# AP62500_6V.net
KiCad netlist of a schematic drawn in Altium Designer
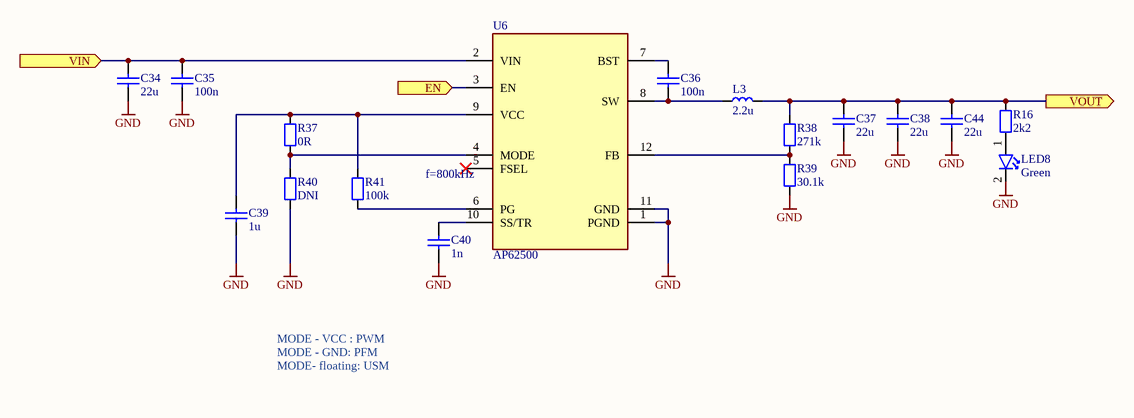
[diagram p0: AP62500_6V.SchDoc]

(export (version "E")
  (design (tool "Eeschema 10.0.6"))
  (components
    (comp (ref "C34")
      (value "22u")
      (footprint "C_1206_3216Metric_IPC_N")
      (description "Generic MLCC with 1206 Footprint")
      (libsource (lib "database_library") (part "Capacitor_unpol"))
    )
    (comp (ref "C35")
      (value "100n")
      (footprint "C_0603_1608Metric_IPC_N")
      (description "Generic MLCC with 0603 Footprint")
      (libsource (lib "database_library") (part "Capacitor_unpol"))
    )
    (comp (ref "C36")
      (value "100n")
      (footprint "C_0402_1005Metric_IPC_N")
      (description "Generic MLCC with 0402 Footprint")
      (libsource (lib "database_library") (part "Capacitor_unpol"))
    )
    (comp (ref "C37")
      (value "22u")
      (footprint "C_1206_3216Metric_IPC_N")
      (description "Generic MLCC with 1206 Footprint")
      (libsource (lib "database_library") (part "Capacitor_unpol"))
    )
    (comp (ref "C38")
      (value "22u")
      (footprint "C_1206_3216Metric_IPC_N")
      (description "Generic MLCC with 1206 Footprint")
      (libsource (lib "database_library") (part "Capacitor_unpol"))
    )
    (comp (ref "C39")
      (value "1u")
      (footprint "C_0603_1608Metric_IPC_N")
      (description "Generic MLCC with 0603 Footprint")
      (libsource (lib "database_library") (part "Capacitor_unpol"))
    )
    (comp (ref "C40")
      (value "1n")
      (footprint "C_0402_1005Metric_IPC_N")
      (description "Generic MLCC with 0402 Footprint")
      (libsource (lib "database_library") (part "Capacitor_unpol"))
    )
    (comp (ref "C44")
      (value "22u")
      (footprint "C_1206_3216Metric_IPC_N")
      (description "Generic MLCC with 1206 Footprint")
      (libsource (lib "database_library") (part "Capacitor_unpol"))
    )
    (comp (ref "L3")
      (value "2.2u")
      (footprint "AVX_LMLP07A7")
      (description "Power Inductor, 2.2u, 8A, -, 20m, 20%, LMLP07A7")
      (fields (field (name "TOLERANCE") "20%") (field (name "MANUFACTURER") "Kyocera/AVX"))
      (libsource (lib "database_library") (part "Inductor"))
    )
    (comp (ref "LED8")
      (value "Green")
      (footprint "LED_0603_1806Metric_IPC_N")
      (description "MLCC, Low Current, Green, 2.2V, 20mA, 0603")
      (fields
        (field (name "MANUFACTURER") "Broadcom / Avago")
        (field (name "MANUFACTURER PART NUMBER") "HSMG-C190")
      )
      (libsource (lib "database_library") (part "LED"))
    )
    (comp (ref "R16")
      (value "2k2")
      (footprint "R_0402_1005Metric_IPC_N")
      (description "Generic Chip Resistor with 0402 Footprint")
      (libsource (lib "database_library") (part "Resistor"))
    )
    (comp (ref "R37")
      (value "0R")
      (footprint "R_0402_1005Metric_IPC_N")
      (description "Generic Chip Resistor with 0402 Footprint")
      (libsource (lib "database_library") (part "Resistor"))
    )
    (comp (ref "R38")
      (value "271k")
      (footprint "R_0402_1005Metric_IPC_N")
      (description "Generic Chip Resistor with 0402 Footprint")
      (libsource (lib "database_library") (part "Resistor"))
    )
    (comp (ref "R39")
      (value "30.1k")
      (footprint "R_0402_1005Metric_IPC_N")
      (description "Generic Chip Resistor with 0402 Footprint")
      (libsource (lib "database_library") (part "Resistor"))
    )
    (comp (ref "R40")
      (value "DNI")
      (footprint "R_0402_1005Metric_IPC_N")
      (description "Generic Chip Resistor with 0402 Footprint")
      (libsource (lib "database_library") (part "Resistor"))
    )
    (comp (ref "R41")
      (value "100k")
      (footprint "R_0402_1005Metric_IPC_N")
      (description "Generic Chip Resistor with 0402 Footprint")
      (libsource (lib "database_library") (part "Resistor"))
    )
    (comp (ref "U6")
      (value "AP62500")
      (footprint "V-QFN2030-12-Type-A_3.05x2.05mm_P0.5mm")
      (fields (field (name "MANUFACTURER") "Diodes Incorporated"))
      (libsource (lib "database_library") (part "AP62500"))
    )
  )
  (nets
    (net (code "1") (name "/EN") (class "Default")
      (node (ref "U6") (pin "3") (pinfunction "EN_3") (pintype "passive"))
    )
    (net (code "2") (name "/VIN") (class "Default")
      (node (ref "C34") (pin "2") (pinfunction "2_2") (pintype "passive"))
      (node (ref "C35") (pin "2") (pinfunction "2_2") (pintype "passive"))
      (node (ref "U6") (pin "2") (pinfunction "VIN_2") (pintype "passive"))
    )
    (net (code "3") (name "/VOUT") (class "Default")
      (node (ref "C37") (pin "2") (pinfunction "2_2") (pintype "passive"))
      (node (ref "C38") (pin "2") (pinfunction "2_2") (pintype "passive"))
      (node (ref "C44") (pin "2") (pinfunction "2_2") (pintype "passive"))
      (node (ref "L3") (pin "2") (pinfunction "2_2") (pintype "passive"))
      (node (ref "R16") (pin "1") (pinfunction "1_1") (pintype "passive"))
      (node (ref "R38") (pin "2") (pinfunction "2_2") (pintype "passive"))
    )
    (net (code "4") (name "GND") (class "Default")
      (node (ref "C34") (pin "1") (pinfunction "1_1") (pintype "passive"))
      (node (ref "C35") (pin "1") (pinfunction "1_1") (pintype "passive"))
      (node (ref "C37") (pin "1") (pinfunction "1_1") (pintype "passive"))
      (node (ref "C38") (pin "1") (pinfunction "1_1") (pintype "passive"))
      (node (ref "C39") (pin "1") (pinfunction "1_1") (pintype "passive"))
      (node (ref "C40") (pin "1") (pinfunction "1_1") (pintype "passive"))
      (node (ref "C44") (pin "1") (pinfunction "1_1") (pintype "passive"))
      (node (ref "LED8") (pin "2") (pinfunction "2_2") (pintype "passive"))
      (node (ref "R39") (pin "1") (pinfunction "1_1") (pintype "passive"))
      (node (ref "R40") (pin "1") (pinfunction "1_1") (pintype "passive"))
      (node (ref "U6") (pin "1") (pinfunction "PGND_1") (pintype "passive"))
      (node (ref "U6") (pin "11") (pinfunction "GND_11") (pintype "passive"))
    )
    (net (code "5") (name "Net-(LED8-Pad1)") (class "Default")
      (node (ref "LED8") (pin "1") (pinfunction "1_1") (pintype "passive"))
      (node (ref "R16") (pin "2") (pinfunction "2_2") (pintype "passive"))
    )
    (net (code "6") (name "Net-(U6-BST)") (class "Default")
      (node (ref "C36") (pin "2") (pinfunction "2_2") (pintype "passive"))
      (node (ref "U6") (pin "7") (pinfunction "BST_7") (pintype "passive"))
    )
    (net (code "7") (name "Net-(U6-FB)") (class "Default")
      (node (ref "R38") (pin "1") (pinfunction "1_1") (pintype "passive"))
      (node (ref "R39") (pin "2") (pinfunction "2_2") (pintype "passive"))
      (node (ref "U6") (pin "12") (pinfunction "FB_12") (pintype "passive"))
    )
    (net (code "8") (name "Net-(U6-MODE)") (class "Default")
      (node (ref "R37") (pin "1") (pinfunction "1_1") (pintype "passive"))
      (node (ref "R40") (pin "2") (pinfunction "2_2") (pintype "passive"))
      (node (ref "U6") (pin "4") (pinfunction "MODE_4") (pintype "passive"))
    )
    (net (code "9") (name "Net-(U6-PG)") (class "Default")
      (node (ref "R41") (pin "1") (pinfunction "1_1") (pintype "passive"))
      (node (ref "U6") (pin "6") (pinfunction "PG_6") (pintype "open_collector"))
    )
    (net (code "10") (name "Net-(U6-SS{slash}TR)") (class "Default")
      (node (ref "C40") (pin "2") (pinfunction "2_2") (pintype "passive"))
      (node (ref "U6") (pin "10") (pinfunction "SS/TR_10") (pintype "passive"))
    )
    (net (code "11") (name "Net-(U6-SW)") (class "Default")
      (node (ref "C36") (pin "1") (pinfunction "1_1") (pintype "passive"))
      (node (ref "L3") (pin "1") (pinfunction "1_1") (pintype "passive"))
      (node (ref "U6") (pin "8") (pinfunction "SW_8") (pintype "passive"))
    )
    (net (code "12") (name "Net-(U6-VCC)") (class "Default")
      (node (ref "C39") (pin "2") (pinfunction "2_2") (pintype "passive"))
      (node (ref "R37") (pin "2") (pinfunction "2_2") (pintype "passive"))
      (node (ref "R41") (pin "2") (pinfunction "2_2") (pintype "passive"))
      (node (ref "U6") (pin "9") (pinfunction "VCC_9") (pintype "passive"))
    )
    (net (code "13") (name "unconnected-(U6-FSEL-Pad5)") (class "Default")
      (node (ref "U6") (pin "5") (pinfunction "FSEL_5") (pintype "passive+no_connect"))
    )
  )
)
